# 02_MCU.net
KiCad netlist of a schematic drawn in Altium Designer
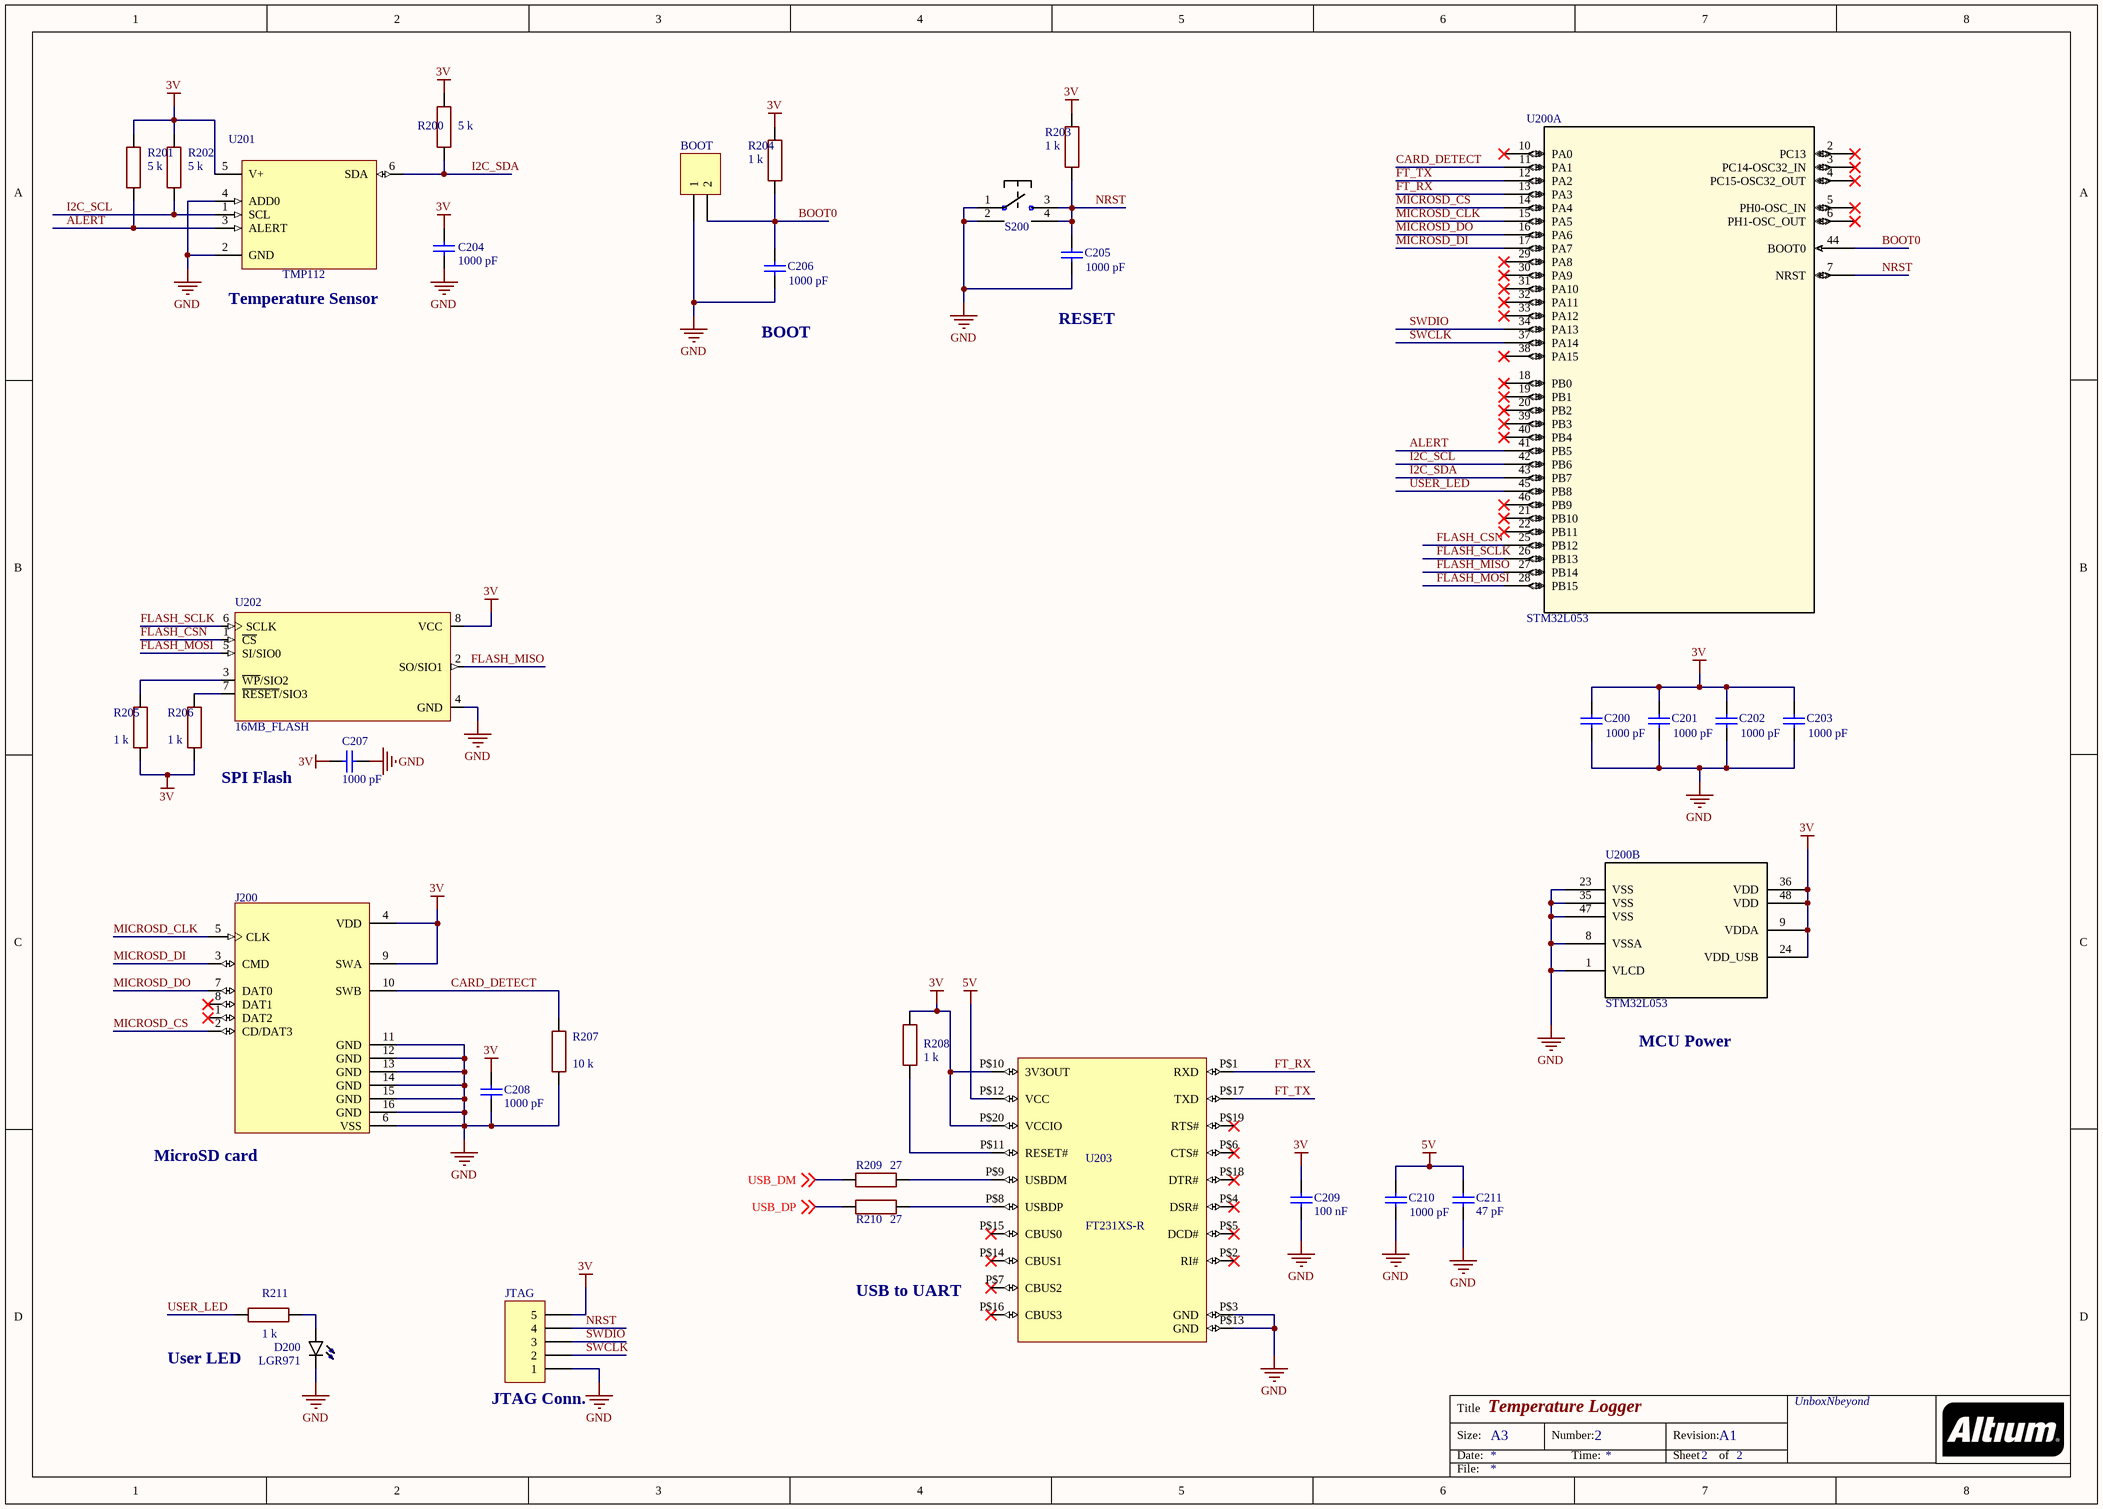
[diagram p0: 02_MCU.SchDoc]

(export (version "E")
  (design (tool "Eeschema 10.0.6"))
  (components
    (comp (ref "BOOT")
      (value "~")
      (footprint "HDR1X2")
      (description "Header, 2-Pin")
      (fields (field (name "PUBLISHER") "Altium Limited"))
      (libsource (lib "Miscellaneous Connectors") (part "Header 2"))
    )
    (comp (ref "C200")
      (value "1000 pF")
      (footprint "C0805")
      (description "CAP CER 1000PF 100V X7R 0805")
      (fields
        (field (name "MANUFACTURER") "KEMET")
        (field (name "MANUFACTURER PART NUMBER") "C0805C102K1RACTU")
      )
      (libsource (lib "temperature_logger_lib") (part "Cap-1000pF"))
    )
    (comp (ref "C201")
      (value "1000 pF")
      (footprint "C0805")
      (description "CAP CER 1000PF 100V X7R 0805")
      (fields
        (field (name "MANUFACTURER") "KEMET")
        (field (name "MANUFACTURER PART NUMBER") "C0805C102K1RACTU")
      )
      (libsource (lib "temperature_logger_lib") (part "Cap-1000pF"))
    )
    (comp (ref "C202")
      (value "1000 pF")
      (footprint "C0805")
      (description "CAP CER 1000PF 100V X7R 0805")
      (fields
        (field (name "MANUFACTURER") "KEMET")
        (field (name "MANUFACTURER PART NUMBER") "C0805C102K1RACTU")
      )
      (libsource (lib "temperature_logger_lib") (part "Cap-1000pF"))
    )
    (comp (ref "C203")
      (value "1000 pF")
      (footprint "C0805")
      (description "CAP CER 1000PF 100V X7R 0805")
      (fields
        (field (name "MANUFACTURER") "KEMET")
        (field (name "MANUFACTURER PART NUMBER") "C0805C102K1RACTU")
      )
      (libsource (lib "temperature_logger_lib") (part "Cap-1000pF"))
    )
    (comp (ref "C204")
      (value "1000 pF")
      (footprint "C0805")
      (description "CAP CER 1000PF 100V X7R 0805")
      (fields
        (field (name "MANUFACTURER") "KEMET")
        (field (name "MANUFACTURER PART NUMBER") "C0805C102K1RACTU")
      )
      (libsource (lib "temperature_logger_lib") (part "Cap-1000pF"))
    )
    (comp (ref "C205")
      (value "1000 pF")
      (footprint "C0805")
      (description "CAP CER 1000PF 100V X7R 0805")
      (fields
        (field (name "MANUFACTURER") "KEMET")
        (field (name "MANUFACTURER PART NUMBER") "C0805C102K1RACTU")
      )
      (libsource (lib "temperature_logger_lib") (part "Cap-1000pF"))
    )
    (comp (ref "C206")
      (value "1000 pF")
      (footprint "C0805")
      (description "CAP CER 1000PF 100V X7R 0805")
      (fields
        (field (name "MANUFACTURER") "KEMET")
        (field (name "MANUFACTURER PART NUMBER") "C0805C102K1RACTU")
      )
      (libsource (lib "temperature_logger_lib") (part "Cap-1000pF"))
    )
    (comp (ref "C207")
      (value "1000 pF")
      (footprint "C0805")
      (description "CAP CER 1000PF 100V X7R 0805")
      (fields
        (field (name "MANUFACTURER") "KEMET")
        (field (name "MANUFACTURER PART NUMBER") "C0805C102K1RACTU")
      )
      (libsource (lib "temperature_logger_lib") (part "Cap-1000pF"))
    )
    (comp (ref "C208")
      (value "1000 pF")
      (footprint "C0805")
      (description "CAP CER 1000PF 100V X7R 0805")
      (fields
        (field (name "MANUFACTURER") "KEMET")
        (field (name "MANUFACTURER PART NUMBER") "C0805C102K1RACTU")
      )
      (libsource (lib "temperature_logger_lib") (part "Cap-1000pF"))
    )
    (comp (ref "C209")
      (value "100 nF")
      (footprint "C0805")
      (description "CAP CER 0.1UF 50V X7R 0805")
      (fields
        (field (name "MANUFACTURER") "KEMET")
        (field (name "MANUFACTURER PART NUMBER") "C0805X104K5RACTU")
      )
      (libsource (lib "temperature_logger_lib") (part "Cap-100nF"))
    )
    (comp (ref "C210")
      (value "1000 pF")
      (footprint "C0805")
      (description "CAP CER 1000PF 100V X7R 0805")
      (fields
        (field (name "MANUFACTURER") "KEMET")
        (field (name "MANUFACTURER PART NUMBER") "C0805C102K1RACTU")
      )
      (libsource (lib "temperature_logger_lib") (part "Cap-1000pF"))
    )
    (comp (ref "C211")
      (value "47 pF")
      (footprint "C0805")
      (description "CAP CER 47PF 1KV C0G/NP0 0805")
      (fields
        (field (name "MANUFACTURER") "KEMET")
        (field (name "MANUFACTURER PART NUMBER") "C0805C470JDGACTU")
      )
      (libsource (lib "temperature_logger_lib") (part "Cap-47pF"))
    )
    (comp (ref "D200")
      (value "LGR971")
      (footprint "D0805")
      (description "LED GREEN DIFFUSED 0805 SMD")
      (fields
        (field (name "MANUFACTURER") "Osram Opto")
        (field (name "MANUFACTURER PART NUMBER") "LG R971-KN-1")
      )
      (libsource (lib "temperature_logger_lib") (part "LGR971"))
    )
    (comp (ref "J200")
      (value "MicroSD")
      (footprint "MicroSD")
      (description "MICRO SD PUSH PUSH LOW PROFILE TYPE")
      (fields
        (field (name "MANUFACTURER PART NUMBER") "2201778-1")
        (field (name "MANUFACTURER") "TE Connectivity")
      )
      (libsource (lib "temperature_logger_lib") (part "MicroSD"))
    )
    (comp (ref "JTAG")
      (value "~")
      (footprint "HDR1X5")
      (description "Header, 5-Pin")
      (fields (field (name "PUBLISHER") "Altium Limited"))
      (libsource (lib "Miscellaneous Connectors") (part "Header 5"))
    )
    (comp (ref "R200")
      (value "5 k")
      (footprint "R0805")
      (description "RES SMD 4.7K OHM 0.1% 1/8W 0805")
      (fields
        (field (name "MANUFACTURER") "Panasonic Electronic Components")
        (field (name "MANUFACTURER PART NUMBER") "ERA-6AEB472V")
      )
      (libsource (lib "temperature_logger_lib") (part "Res-5k"))
    )
    (comp (ref "R201")
      (value "5 k")
      (footprint "R0805")
      (description "RES SMD 4.7K OHM 0.1% 1/8W 0805")
      (fields
        (field (name "MANUFACTURER") "Panasonic Electronic Components")
        (field (name "MANUFACTURER PART NUMBER") "ERA-6AEB472V")
      )
      (libsource (lib "temperature_logger_lib") (part "Res-5k"))
    )
    (comp (ref "R202")
      (value "5 k")
      (footprint "R0805")
      (description "RES SMD 4.7K OHM 0.1% 1/8W 0805")
      (fields
        (field (name "MANUFACTURER") "Panasonic Electronic Components")
        (field (name "MANUFACTURER PART NUMBER") "ERA-6AEB472V")
      )
      (libsource (lib "temperature_logger_lib") (part "Res-5k"))
    )
    (comp (ref "R203")
      (value "1 k")
      (footprint "R0805")
      (description "RES 1K OHM 0.1% 1/5W 0805")
      (fields
        (field (name "MANUFACTURER") "Vishay Dale")
        (field (name "MANUFACTURER PART NUMBER") "TNPW08051K00BEEA")
      )
      (libsource (lib "") (part "Res-1k_1"))
    )
    (comp (ref "R204")
      (value "1 k")
      (footprint "R0805")
      (description "RES 1K OHM 0.1% 1/5W 0805")
      (fields
        (field (name "MANUFACTURER") "Vishay Dale")
        (field (name "MANUFACTURER PART NUMBER") "TNPW08051K00BEEA")
      )
      (libsource (lib "") (part "Res-1k_1"))
    )
    (comp (ref "R205")
      (value "1 k")
      (footprint "R0805")
      (description "RES 1K OHM 0.1% 1/5W 0805")
      (fields
        (field (name "MANUFACTURER") "Vishay Dale")
        (field (name "MANUFACTURER PART NUMBER") "TNPW08051K00BEEA")
      )
      (libsource (lib "") (part "Res-1k_2"))
    )
    (comp (ref "R206")
      (value "1 k")
      (footprint "R0805")
      (description "RES 1K OHM 0.1% 1/5W 0805")
      (fields
        (field (name "MANUFACTURER") "Vishay Dale")
        (field (name "MANUFACTURER PART NUMBER") "TNPW08051K00BEEA")
      )
      (libsource (lib "") (part "Res-1k_2"))
    )
    (comp (ref "R207")
      (value "10 k")
      (footprint "R0805")
      (description "RES SMD 10K OHM 0.1% 1/8W 0805")
      (fields
        (field (name "MANUFACTURER") "Panasonic Electronic Components")
        (field (name "MANUFACTURER PART NUMBER") "ERA-6AEB103V")
      )
      (libsource (lib "temperature_logger_lib") (part "Res-10k"))
    )
    (comp (ref "R208")
      (value "1 k")
      (footprint "R0805")
      (description "RES 1K OHM 0.1% 1/5W 0805")
      (fields
        (field (name "MANUFACTURER") "Vishay Dale")
        (field (name "MANUFACTURER PART NUMBER") "TNPW08051K00BEEA")
      )
      (libsource (lib "") (part "Res-1k_1"))
    )
    (comp (ref "R209")
      (value "27")
      (footprint "R0805")
      (description "RES SMD 27 OHM 5% 1/8W 0805")
      (fields
        (field (name "MANUFACTURER") "Panasonic Electronic Components")
        (field (name "MANUFACTURER PART NUMBER") "ERJ-6GEYJ270V")
      )
      (libsource (lib "temperature_logger_lib") (part "Res-27"))
    )
    (comp (ref "R210")
      (value "27")
      (footprint "R0805")
      (description "RES SMD 27 OHM 5% 1/8W 0805")
      (fields
        (field (name "MANUFACTURER") "Panasonic Electronic Components")
        (field (name "MANUFACTURER PART NUMBER") "ERJ-6GEYJ270V")
      )
      (libsource (lib "temperature_logger_lib") (part "Res-27"))
    )
    (comp (ref "R211")
      (value "1 k")
      (footprint "R0805")
      (description "RES 1K OHM 0.1% 1/5W 0805")
      (fields
        (field (name "MANUFACTURER") "Vishay Dale")
        (field (name "MANUFACTURER PART NUMBER") "TNPW08051K00BEEA")
      )
      (libsource (lib "temperature_logger_lib") (part "Res-1k"))
    )
    (comp (ref "S200")
      (value "Switch_tactile")
      (footprint "Tactile1")
      (description "SWITCH TACTILE SPST-NO 0.05A 12V")
      (fields
        (field (name "MANUFACTURER") "C&K Components")
        (field (name "MANUFACTURER PART NUMBER") "PTS645SM43SMTR")
      )
      (libsource (lib "temperature_logger_lib") (part "Switch_tactile"))
    )
    (comp (ref "U200")
      (value "STM32L053")
      (footprint "LQFP48-7x7mm")
      (description "IC MCU 32BIT 64KB FLASH 48LQFP")
      (fields
        (field (name "MANUFACTURER PART NUMBER") "STM32L053C8T6")
        (field (name "MANUFACTURER") "STMicroelectronics")
      )
      (libsource (lib "temperature_logger_lib") (part "STM32L0x3CL4"))
    )
    (comp (ref "U201")
      (value "TMP112")
      (footprint "SOT563")
      (fields
        (field (name "MANUFACTURER PART NUMBER") "TMP112AIDRLT")
        (field (name "MANUFACTURER") "Texas Instruments")
      )
      (libsource (lib "temperature_logger_lib") (part "TMP112AIDRLT"))
    )
    (comp (ref "U202")
      (value "16MB_FLASH")
      (footprint "8-SOIC")
      (description "IC FLASH 16M SPI 80MHZ 8SOP")
      (fields
        (field (name "MANUFACTURER PART NUMBER") "MX25R1635FM2IL0")
        (field (name "MANUFACTURER") "Macronix")
      )
      (libsource (lib "temperature_logger_lib") (part "MX25R1635"))
    )
    (comp (ref "U203")
      (value "FT231XS-R")
      (footprint "SSOP20")
      (description "USB Full Speed to Full Handshake UART with USB Charger Detection")
      (fields (field (name "MF") "FTDI,"))
      (libsource (lib "temperature_logger_lib") (part "FT231XS-R"))
    )
  )
  (nets
    (net (code "1") (name "/ALERT") (class "Default")
      (node (ref "R201") (pin "2") (pinfunction "2_2") (pintype "passive"))
      (node (ref "U200") (pin "41") (pinfunction "PB5_41") (pintype "bidirectional"))
      (node (ref "U201") (pin "3") (pinfunction "ALERT_3") (pintype "input"))
    )
    (net (code "2") (name "/BOOT0") (class "Default")
      (node (ref "BOOT") (pin "2") (pinfunction "2_2") (pintype "passive"))
      (node (ref "C206") (pin "2") (pinfunction "2_2") (pintype "passive"))
      (node (ref "R204") (pin "2") (pinfunction "2_2") (pintype "passive"))
      (node (ref "U200") (pin "44") (pinfunction "BOOT0_44") (pintype "input"))
    )
    (net (code "3") (name "/CARD_DETECT") (class "Default")
      (node (ref "J200") (pin "10") (pinfunction "SWB_10") (pintype "passive"))
      (node (ref "R207") (pin "1") (pinfunction "1_1") (pintype "passive"))
      (node (ref "U200") (pin "11") (pinfunction "PA1_11") (pintype "bidirectional"))
    )
    (net (code "4") (name "/FLASH_CSN") (class "Default")
      (node (ref "U200") (pin "25") (pinfunction "PB12_25") (pintype "bidirectional"))
      (node (ref "U202") (pin "1") (pinfunction "~{CS}_1") (pintype "input"))
    )
    (net (code "5") (name "/FLASH_MISO") (class "Default")
      (node (ref "U200") (pin "27") (pinfunction "PB14_27") (pintype "bidirectional"))
      (node (ref "U202") (pin "2") (pinfunction "SO/SIO1_2") (pintype "output"))
    )
    (net (code "6") (name "/FLASH_MOSI") (class "Default")
      (node (ref "U200") (pin "28") (pinfunction "PB15_28") (pintype "bidirectional"))
      (node (ref "U202") (pin "5") (pinfunction "SI/SIO0_5") (pintype "input"))
    )
    (net (code "7") (name "/FLASH_SCLK") (class "Default")
      (node (ref "U200") (pin "26") (pinfunction "PB13_26") (pintype "bidirectional"))
      (node (ref "U202") (pin "6") (pinfunction "SCLK_6") (pintype "input"))
    )
    (net (code "8") (name "/FT_RX") (class "Default")
      (node (ref "U200") (pin "13") (pinfunction "PA3_13") (pintype "bidirectional"))
      (node (ref "U203") (pin "P$1") (pinfunction "RXD_P$1") (pintype "bidirectional"))
    )
    (net (code "9") (name "/FT_TX") (class "Default")
      (node (ref "U200") (pin "12") (pinfunction "PA2_12") (pintype "bidirectional"))
      (node (ref "U203") (pin "P$17") (pinfunction "TXD_P$17") (pintype "bidirectional"))
    )
    (net (code "10") (name "/I2C_SCL") (class "Default")
      (node (ref "R202") (pin "2") (pinfunction "2_2") (pintype "passive"))
      (node (ref "U200") (pin "42") (pinfunction "PB6_42") (pintype "bidirectional"))
      (node (ref "U201") (pin "1") (pinfunction "SCL_1") (pintype "input"))
    )
    (net (code "11") (name "/I2C_SDA") (class "Default")
      (node (ref "R200") (pin "2") (pinfunction "2_2") (pintype "passive"))
      (node (ref "U200") (pin "43") (pinfunction "PB7_43") (pintype "bidirectional"))
      (node (ref "U201") (pin "6") (pinfunction "SDA_6") (pintype "bidirectional"))
    )
    (net (code "12") (name "/MICROSD_CLK") (class "Default")
      (node (ref "J200") (pin "5") (pinfunction "CLK_5") (pintype "input"))
      (node (ref "U200") (pin "15") (pinfunction "PA5_15") (pintype "bidirectional"))
    )
    (net (code "13") (name "/MICROSD_CS") (class "Default")
      (node (ref "J200") (pin "2") (pinfunction "CD/DAT3_2") (pintype "bidirectional"))
      (node (ref "U200") (pin "14") (pinfunction "PA4_14") (pintype "bidirectional"))
    )
    (net (code "14") (name "/MICROSD_DI") (class "Default")
      (node (ref "J200") (pin "3") (pinfunction "CMD_3") (pintype "bidirectional"))
      (node (ref "U200") (pin "17") (pinfunction "PA7_17") (pintype "bidirectional"))
    )
    (net (code "15") (name "/MICROSD_DO") (class "Default")
      (node (ref "J200") (pin "7") (pinfunction "DAT0_7") (pintype "bidirectional"))
      (node (ref "U200") (pin "16") (pinfunction "PA6_16") (pintype "bidirectional"))
    )
    (net (code "16") (name "/NRST") (class "Default")
      (node (ref "C205") (pin "2") (pinfunction "2_2") (pintype "passive"))
      (node (ref "JTAG") (pin "4") (pinfunction "4_4") (pintype "passive"))
      (node (ref "R203") (pin "2") (pinfunction "2_2") (pintype "passive"))
      (node (ref "S200") (pin "3") (pinfunction "P$2_3") (pintype "passive"))
      (node (ref "S200") (pin "4") (pinfunction "P$2_4") (pintype "passive"))
      (node (ref "U200") (pin "7") (pinfunction "NRST_7") (pintype "bidirectional"))
    )
    (net (code "17") (name "/SWCLK") (class "Default")
      (node (ref "JTAG") (pin "2") (pinfunction "2_2") (pintype "passive"))
      (node (ref "U200") (pin "37") (pinfunction "PA14_37") (pintype "bidirectional"))
    )
    (net (code "18") (name "/SWDIO") (class "Default")
      (node (ref "JTAG") (pin "3") (pinfunction "3_3") (pintype "passive"))
      (node (ref "U200") (pin "34") (pinfunction "PA13_34") (pintype "bidirectional"))
    )
    (net (code "19") (name "/USER_LED") (class "Default")
      (node (ref "R211") (pin "2") (pinfunction "2_2") (pintype "passive"))
      (node (ref "U200") (pin "45") (pinfunction "PB8_45") (pintype "bidirectional"))
    )
    (net (code "20") (name "3V") (class "Default")
      (node (ref "C200") (pin "2") (pinfunction "2_2") (pintype "passive"))
      (node (ref "C201") (pin "2") (pinfunction "2_2") (pintype "passive"))
      (node (ref "C202") (pin "2") (pinfunction "2_2") (pintype "passive"))
      (node (ref "C203") (pin "2") (pinfunction "2_2") (pintype "passive"))
      (node (ref "C204") (pin "2") (pinfunction "2_2") (pintype "passive"))
      (node (ref "C207") (pin "2") (pinfunction "2_2") (pintype "passive"))
      (node (ref "C208") (pin "1") (pinfunction "1_1") (pintype "passive"))
      (node (ref "C209") (pin "2") (pinfunction "2_2") (pintype "passive"))
      (node (ref "J200") (pin "4") (pinfunction "VDD_4") (pintype "power_in"))
      (node (ref "J200") (pin "9") (pinfunction "SWA_9") (pintype "passive"))
      (node (ref "JTAG") (pin "5") (pinfunction "5_5") (pintype "passive"))
      (node (ref "R200") (pin "1") (pinfunction "1_1") (pintype "passive"))
      (node (ref "R201") (pin "1") (pinfunction "1_1") (pintype "passive"))
      (node (ref "R202") (pin "1") (pinfunction "1_1") (pintype "passive"))
      (node (ref "R203") (pin "1") (pinfunction "1_1") (pintype "passive"))
      (node (ref "R204") (pin "1") (pinfunction "1_1") (pintype "passive"))
      (node (ref "R205") (pin "1") (pinfunction "1_1") (pintype "passive"))
      (node (ref "R206") (pin "1") (pinfunction "1_1") (pintype "passive"))
      (node (ref "R208") (pin "1") (pinfunction "1_1") (pintype "passive"))
      (node (ref "U200") (pin "24") (pinfunction "VDD_USB_24") (pintype "power_in"))
      (node (ref "U200") (pin "36") (pinfunction "VDD_36") (pintype "power_in"))
      (node (ref "U200") (pin "48") (pinfunction "VDD_48") (pintype "power_in"))
      (node (ref "U200") (pin "9") (pinfunction "VDDA_9") (pintype "power_in"))
      (node (ref "U201") (pin "5") (pinfunction "V+_5") (pintype "power_in"))
      (node (ref "U202") (pin "8") (pinfunction "VCC_8") (pintype "power_in"))
      (node (ref "U203") (pin "P$10") (pinfunction "3V3OUT_P$10") (pintype "bidirectional"))
      (node (ref "U203") (pin "P$20") (pinfunction "VCCIO_P$20") (pintype "bidirectional"))
    )
    (net (code "21") (name "5V") (class "Default")
      (node (ref "C210") (pin "2") (pinfunction "2_2") (pintype "passive"))
      (node (ref "C211") (pin "2") (pinfunction "2_2") (pintype "passive"))
      (node (ref "U203") (pin "P$12") (pinfunction "VCC_P$12") (pintype "bidirectional"))
    )
    (net (code "22") (name "GND") (class "Default")
      (node (ref "BOOT") (pin "1") (pinfunction "1_1") (pintype "passive"))
      (node (ref "C200") (pin "1") (pinfunction "1_1") (pintype "passive"))
      (node (ref "C201") (pin "1") (pinfunction "1_1") (pintype "passive"))
      (node (ref "C202") (pin "1") (pinfunction "1_1") (pintype "passive"))
      (node (ref "C203") (pin "1") (pinfunction "1_1") (pintype "passive"))
      (node (ref "C204") (pin "1") (pinfunction "1_1") (pintype "passive"))
      (node (ref "C205") (pin "1") (pinfunction "1_1") (pintype "passive"))
      (node (ref "C206") (pin "1") (pinfunction "1_1") (pintype "passive"))
      (node (ref "C207") (pin "1") (pinfunction "1_1") (pintype "passive"))
      (node (ref "C208") (pin "2") (pinfunction "2_2") (pintype "passive"))
      (node (ref "C209") (pin "1") (pinfunction "1_1") (pintype "passive"))
      (node (ref "C210") (pin "1") (pinfunction "1_1") (pintype "passive"))
      (node (ref "C211") (pin "1") (pinfunction "1_1") (pintype "passive"))
      (node (ref "D200") (pin "C") (pinfunction "C_C") (pintype "passive"))
      (node (ref "J200") (pin "11") (pinfunction "GND_11") (pintype "power_in"))
      (node (ref "J200") (pin "12") (pinfunction "GND_12") (pintype "power_in"))
      (node (ref "J200") (pin "13") (pinfunction "GND_13") (pintype "power_in"))
      (node (ref "J200") (pin "14") (pinfunction "GND_14") (pintype "power_in"))
      (node (ref "J200") (pin "15") (pinfunction "GND_15") (pintype "power_in"))
      (node (ref "J200") (pin "16") (pinfunction "GND_16") (pintype "power_in"))
      (node (ref "J200") (pin "6") (pinfunction "VSS_6") (pintype "power_in"))
      (node (ref "JTAG") (pin "1") (pinfunction "1_1") (pintype "passive"))
      (node (ref "R207") (pin "2") (pinfunction "2_2") (pintype "passive"))
      (node (ref "S200") (pin "1") (pinfunction "P$1_1") (pintype "passive"))
      (node (ref "S200") (pin "2") (pinfunction "P$1_2") (pintype "passive"))
      (node (ref "U200") (pin "1") (pinfunction "VLCD_1") (pintype "power_in"))
      (node (ref "U200") (pin "23") (pinfunction "VSS_23") (pintype "power_in"))
      (node (ref "U200") (pin "35") (pinfunction "VSS_35") (pintype "power_in"))
      (node (ref "U200") (pin "47") (pinfunction "VSS_47") (pintype "power_in"))
      (node (ref "U200") (pin "8") (pinfunction "VSSA_8") (pintype "power_in"))
      (node (ref "U201") (pin "2") (pinfunction "GND_2") (pintype "passive"))
      (node (ref "U201") (pin "4") (pinfunction "ADD0_4") (pintype "input"))
      (node (ref "U202") (pin "4") (pinfunction "GND_4") (pintype "power_in"))
      (node (ref "U203") (pin "P$13") (pinfunction "GND_P$13") (pintype "bidirectional"))
      (node (ref "U203") (pin "P$3") (pinfunction "GND_P$3") (pintype "bidirectional"))
    )
    (net (code "23") (name "Net-(D200-PadA)") (class "Default")
      (node (ref "D200") (pin "A") (pinfunction "A_A") (pintype "passive"))
      (node (ref "R211") (pin "1") (pinfunction "1_1") (pintype "passive"))
    )
    (net (code "24") (name "Net-(U202-~{RESET}{slash}SIO3)") (class "Default")
      (node (ref "R206") (pin "2") (pinfunction "2_2") (pintype "passive"))
      (node (ref "U202") (pin "7") (pinfunction "~{RESET}/SIO3_7") (pintype "bidirectional"))
    )
    (net (code "25") (name "Net-(U202-~{WP}{slash}SIO2)") (class "Default")
      (node (ref "R205") (pin "2") (pinfunction "2_2") (pintype "passive"))
      (node (ref "U202") (pin "3") (pinfunction "~{WP}/SIO2_3") (pintype "bidirectional"))
    )
    (net (code "26") (name "Net-(U203-RESET#)") (class "Default")
      (node (ref "R208") (pin "2") (pinfunction "2_2") (pintype "passive"))
      (node (ref "U203") (pin "P$11") (pinfunction "RESET#_P$11") (pintype "bidirectional"))
    )
    (net (code "27") (name "Net-(U203-USBDM)") (class "Default")
      (node (ref "R209") (pin "1") (pinfunction "1_1") (pintype "passive"))
      (node (ref "U203") (pin "P$9") (pinfunction "USBDM_P$9") (pintype "bidirectional"))
    )
    (net (code "28") (name "Net-(U203-USBDP)") (class "Default")
      (node (ref "R210") (pin "1") (pinfunction "1_1") (pintype "passive"))
      (node (ref "U203") (pin "P$8") (pinfunction "USBDP_P$8") (pintype "bidirectional"))
    )
    (net (code "29") (name "USB_DM") (class "Default")
      (node (ref "R209") (pin "2") (pinfunction "2_2") (pintype "passive"))
    )
    (net (code "30") (name "USB_DP") (class "Default")
      (node (ref "R210") (pin "2") (pinfunction "2_2") (pintype "passive"))
    )
    (net (code "31") (name "unconnected-(J200-DAT1-Pad8)") (class "Default")
      (node (ref "J200") (pin "8") (pinfunction "DAT1_8") (pintype "bidirectional+no_connect"))
    )
    (net (code "32") (name "unconnected-(J200-DAT2-Pad1)") (class "Default")
      (node (ref "J200") (pin "1") (pinfunction "DAT2_1") (pintype "bidirectional+no_connect"))
    )
    (net (code "33") (name "unconnected-(U200A-PA0-Pad10)") (class "Default")
      (node (ref "U200") (pin "10") (pinfunction "PA0_10") (pintype "bidirectional+no_connect"))
    )
    (net (code "34") (name "unconnected-(U200A-PA8-Pad29)") (class "Default")
      (node (ref "U200") (pin "29") (pinfunction "PA8_29") (pintype "bidirectional+no_connect"))
    )
    (net (code "35") (name "unconnected-(U200A-PA9-Pad30)") (class "Default")
      (node (ref "U200") (pin "30") (pinfunction "PA9_30") (pintype "bidirectional+no_connect"))
    )
    (net (code "36") (name "unconnected-(U200A-PA10-Pad31)") (class "Default")
      (node (ref "U200") (pin "31") (pinfunction "PA10_31") (pintype "bidirectional+no_connect"))
    )
    (net (code "37") (name "unconnected-(U200A-PA11-Pad32)") (class "Default")
      (node (ref "U200") (pin "32") (pinfunction "PA11_32") (pintype "bidirectional+no_connect"))
    )
    (net (code "38") (name "unconnected-(U200A-PA12-Pad33)") (class "Default")
      (node (ref "U200") (pin "33") (pinfunction "PA12_33") (pintype "bidirectional+no_connect"))
    )
    (net (code "39") (name "unconnected-(U200A-PA15-Pad38)") (class "Default")
      (node (ref "U200") (pin "38") (pinfunction "PA15_38") (pintype "bidirectional+no_connect"))
    )
    (net (code "40") (name "unconnected-(U200A-PB0-Pad18)") (class "Default")
      (node (ref "U200") (pin "18") (pinfunction "PB0_18") (pintype "bidirectional+no_connect"))
    )
    (net (code "41") (name "unconnected-(U200A-PB1-Pad19)") (class "Default")
      (node (ref "U200") (pin "19") (pinfunction "PB1_19") (pintype "bidirectional+no_connect"))
    )
    (net (code "42") (name "unconnected-(U200A-PB2-Pad20)") (class "Default")
      (node (ref "U200") (pin "20") (pinfunction "PB2_20") (pintype "bidirectional+no_connect"))
    )
    (net (code "43") (name "unconnected-(U200A-PB3-Pad39)") (class "Default")
      (node (ref "U200") (pin "39") (pinfunction "PB3_39") (pintype "bidirectional+no_connect"))
    )
    (net (code "44") (name "unconnected-(U200A-PB4-Pad40)") (class "Default")
      (node (ref "U200") (pin "40") (pinfunction "PB4_40") (pintype "bidirectional+no_connect"))
    )
    (net (code "45") (name "unconnected-(U200A-PB9-Pad46)") (class "Default")
      (node (ref "U200") (pin "46") (pinfunction "PB9_46") (pintype "bidirectional+no_connect"))
    )
    (net (code "46") (name "unconnected-(U200A-PB10-Pad21)") (class "Default")
      (node (ref "U200") (pin "21") (pinfunction "PB10_21") (pintype "bidirectional+no_connect"))
    )
    (net (code "47") (name "unconnected-(U200A-PB11-Pad22)") (class "Default")
      (node (ref "U200") (pin "22") (pinfunction "PB11_22") (pintype "bidirectional+no_connect"))
    )
    (net (code "48") (name "unconnected-(U200A-PC13-Pad2)") (class "Default")
      (node (ref "U200") (pin "2") (pinfunction "PC13_2") (pintype "bidirectional+no_connect"))
    )
    (net (code "49") (name "unconnected-(U200A-PC14-OSC32_IN-Pad3)") (class "Default")
      (node (ref "U200") (pin "3") (pinfunction "PC14-OSC32_IN_3") (pintype "bidirectional+no_connect"))
    )
    (net (code "50") (name "unconnected-(U200A-PC15-OSC32_OUT-Pad4)") (class "Default")
      (node (ref "U200") (pin "4") (pinfunction "PC15-OSC32_OUT_4") (pintype "bidirectional+no_connect"))
    )
    (net (code "51") (name "unconnected-(U200A-PH0-OSC_IN-Pad5)") (class "Default")
      (node (ref "U200") (pin "5") (pinfunction "PH0-OSC_IN_5") (pintype "bidirectional+no_connect"))
    )
    (net (code "52") (name "unconnected-(U200A-PH1-OSC_OUT-Pad6)") (class "Default")
      (node (ref "U200") (pin "6") (pinfunction "PH1-OSC_OUT_6") (pintype "bidirectional+no_connect"))
    )
    (net (code "53") (name "unconnected-(U203-CBUS0-PadP$15)") (class "Default")
      (node (ref "U203") (pin "P$15") (pinfunction "CBUS0_P$15") (pintype "bidirectional+no_connect"))
    )
    (net (code "54") (name "unconnected-(U203-CBUS1-PadP$14)") (class "Default")
      (node (ref "U203") (pin "P$14") (pinfunction "CBUS1_P$14") (pintype "bidirectional+no_connect"))
    )
    (net (code "55") (name "unconnected-(U203-CBUS2-PadP$7)") (class "Default")
      (node (ref "U203") (pin "P$7") (pinfunction "CBUS2_P$7") (pintype "bidirectional+no_connect"))
    )
    (net (code "56") (name "unconnected-(U203-CBUS3-PadP$16)") (class "Default")
      (node (ref "U203") (pin "P$16") (pinfunction "CBUS3_P$16") (pintype "bidirectional+no_connect"))
    )
    (net (code "57") (name "unconnected-(U203-CTS#-PadP$6)") (class "Default")
      (node (ref "U203") (pin "P$6") (pinfunction "CTS#_P$6") (pintype "bidirectional+no_connect"))
    )
    (net (code "58") (name "unconnected-(U203-DCD#-PadP$5)") (class "Default")
      (node (ref "U203") (pin "P$5") (pinfunction "DCD#_P$5") (pintype "bidirectional+no_connect"))
    )
    (net (code "59") (name "unconnected-(U203-DSR#-PadP$4)") (class "Default")
      (node (ref "U203") (pin "P$4") (pinfunction "DSR#_P$4") (pintype "bidirectional+no_connect"))
    )
    (net (code "60") (name "unconnected-(U203-DTR#-PadP$18)") (class "Default")
      (node (ref "U203") (pin "P$18") (pinfunction "DTR#_P$18") (pintype "bidirectional+no_connect"))
    )
    (net (code "61") (name "unconnected-(U203-RI#-PadP$2)") (class "Default")
      (node (ref "U203") (pin "P$2") (pinfunction "RI#_P$2") (pintype "bidirectional+no_connect"))
    )
    (net (code "62") (name "unconnected-(U203-RTS#-PadP$19)") (class "Default")
      (node (ref "U203") (pin "P$19") (pinfunction "RTS#_P$19") (pintype "bidirectional+no_connect"))
    )
  )
)
